# STM32F103C6.net
KiCad netlist of a schematic drawn in Altium Designer
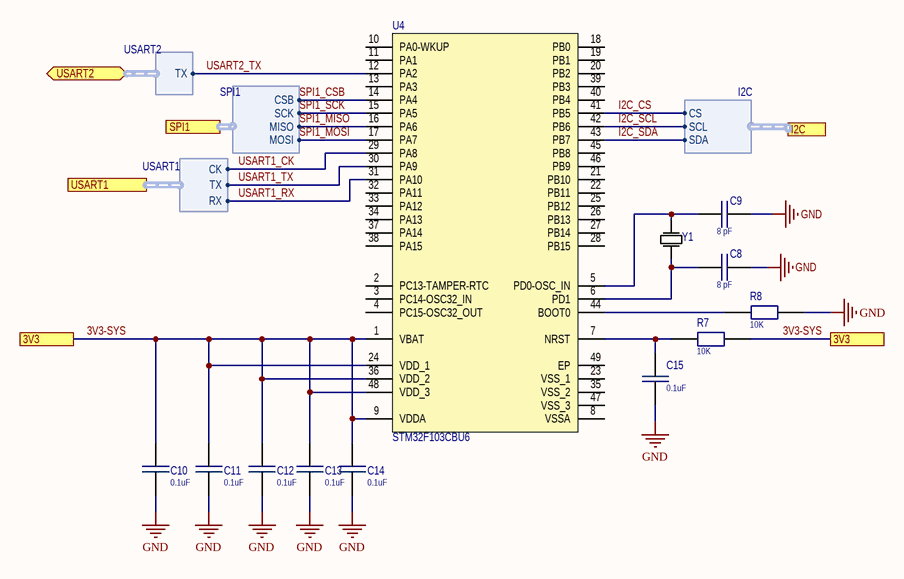
[diagram p0: STM32F103C6.SchDoc]

(export (version "E")
  (design (tool "Eeschema 10.0.6"))
  (components
    (comp (ref "C8")
      (value "8 pF")
      (footprint "C_0805")
      (description "Capacitor")
      (libsource (lib "components") (part "C0805"))
    )
    (comp (ref "C9")
      (value "8 pF")
      (footprint "C_0805")
      (description "Capacitor")
      (libsource (lib "components") (part "C0805"))
    )
    (comp (ref "C10")
      (value "0.1uF")
      (footprint "C_0805")
      (description "Capacitor")
      (libsource (lib "components") (part "C0805"))
    )
    (comp (ref "C11")
      (value "0.1uF")
      (footprint "C_0805")
      (description "Capacitor")
      (libsource (lib "components") (part "C0805"))
    )
    (comp (ref "C12")
      (value "0.1uF")
      (footprint "C_0805")
      (description "Capacitor")
      (libsource (lib "components") (part "C0805"))
    )
    (comp (ref "C13")
      (value "0.1uF")
      (footprint "C_0805")
      (description "Capacitor")
      (libsource (lib "components") (part "C0805"))
    )
    (comp (ref "C14")
      (value "0.1uF")
      (footprint "C_0805")
      (description "Capacitor")
      (libsource (lib "components") (part "C0805"))
    )
    (comp (ref "C15")
      (value "0.1uF")
      (footprint "C_0805")
      (description "Capacitor")
      (libsource (lib "components") (part "C0805"))
    )
    (comp (ref "R7")
      (value "10K")
      (footprint "R_0402")
      (description "Resistor")
      (libsource (lib "components") (part "R0402"))
    )
    (comp (ref "R8")
      (value "10K")
      (footprint "R_0402")
      (description "Resistor")
      (libsource (lib "components") (part "R0402"))
    )
    (comp (ref "U4")
      (value "STM32F103CBU6")
      (footprint "STM-UFQFPN48_M")
      (libsource (lib "modules") (part "STM32F103CBU6"))
    )
    (comp (ref "Y1")
      (value "~")
      (footprint "NX3225GD")
      (description "Crystal Oscillator")
      (libsource (lib "components") (part "NX3225GD"))
    )
  )
  (nets
    (net (code "5") (name "/3V3-SYS") (class "Default")
      (node (ref "C10") (pin "1") (pinfunction "1_1") (pintype "passive"))
      (node (ref "C11") (pin "1") (pinfunction "1_1") (pintype "passive"))
      (node (ref "C12") (pin "1") (pinfunction "1_1") (pintype "passive"))
      (node (ref "C13") (pin "1") (pinfunction "1_1") (pintype "passive"))
      (node (ref "C14") (pin "1") (pinfunction "1_1") (pintype "passive"))
      (node (ref "R7") (pin "2") (pinfunction "2_2") (pintype "passive"))
      (node (ref "U4") (pin "1") (pinfunction "VBAT_1") (pintype "passive"))
      (node (ref "U4") (pin "24") (pinfunction "VDD_1_24") (pintype "passive"))
      (node (ref "U4") (pin "36") (pinfunction "VDD_2_36") (pintype "passive"))
      (node (ref "U4") (pin "48") (pinfunction "VDD_3_48") (pintype "passive"))
      (node (ref "U4") (pin "9") (pinfunction "VDDA_9") (pintype "passive"))
    )
    (net (code "6") (name "/I2C_CS") (class "Default")
      (node (ref "U4") (pin "41") (pinfunction "PB5_41") (pintype "passive"))
    )
    (net (code "7") (name "/I2C_SCL") (class "Default")
      (node (ref "U4") (pin "42") (pinfunction "PB6_42") (pintype "passive"))
    )
    (net (code "8") (name "/I2C_SDA") (class "Default")
      (node (ref "U4") (pin "43") (pinfunction "PB7_43") (pintype "passive"))
    )
    (net (code "9") (name "/SPI1_CSB") (class "Default")
      (node (ref "U4") (pin "14") (pinfunction "PA4_14") (pintype "passive"))
    )
    (net (code "10") (name "/SPI1_MISO") (class "Default")
      (node (ref "U4") (pin "16") (pinfunction "PA6_16") (pintype "passive"))
    )
    (net (code "11") (name "/SPI1_MOSI") (class "Default")
      (node (ref "U4") (pin "17") (pinfunction "PA7_17") (pintype "passive"))
    )
    (net (code "12") (name "/SPI1_SCK") (class "Default")
      (node (ref "U4") (pin "15") (pinfunction "PA5_15") (pintype "passive"))
    )
    (net (code "13") (name "/USART1_CK") (class "Default")
      (node (ref "U4") (pin "29") (pinfunction "PA8_29") (pintype "passive"))
    )
    (net (code "14") (name "/USART1_RX") (class "Default")
      (node (ref "U4") (pin "31") (pinfunction "PA10_31") (pintype "passive"))
    )
    (net (code "15") (name "/USART1_TX") (class "Default")
      (node (ref "U4") (pin "30") (pinfunction "PA9_30") (pintype "passive"))
    )
    (net (code "16") (name "/USART2_TX") (class "Default")
      (node (ref "U4") (pin "12") (pinfunction "PA2_12") (pintype "passive"))
    )
    (net (code "21") (name "GND") (class "Default")
      (node (ref "C10") (pin "2") (pinfunction "2_2") (pintype "passive"))
      (node (ref "C11") (pin "2") (pinfunction "2_2") (pintype "passive"))
      (node (ref "C12") (pin "2") (pinfunction "2_2") (pintype "passive"))
      (node (ref "C13") (pin "2") (pinfunction "2_2") (pintype "passive"))
      (node (ref "C14") (pin "2") (pinfunction "2_2") (pintype "passive"))
      (node (ref "C15") (pin "1") (pinfunction "1_1") (pintype "passive"))
      (node (ref "C8") (pin "2") (pinfunction "2_2") (pintype "passive"))
      (node (ref "C9") (pin "1") (pinfunction "1_1") (pintype "passive"))
      (node (ref "R8") (pin "2") (pinfunction "2_2") (pintype "passive"))
    )
    (net (code "22") (name "Net-(U4-BOOT0)") (class "Default")
      (node (ref "R8") (pin "1") (pinfunction "1_1") (pintype "passive"))
      (node (ref "U4") (pin "44") (pinfunction "BOOT0_44") (pintype "passive"))
    )
    (net (code "23") (name "Net-(U4-NRST)") (class "Default")
      (node (ref "C15") (pin "2") (pinfunction "2_2") (pintype "passive"))
      (node (ref "R7") (pin "1") (pinfunction "1_1") (pintype "passive"))
      (node (ref "U4") (pin "7") (pinfunction "NRST_7") (pintype "passive"))
    )
    (net (code "24") (name "Net-(U4-PD0-OSC_IN)") (class "Default")
      (node (ref "C9") (pin "2") (pinfunction "2_2") (pintype "passive"))
      (node (ref "U4") (pin "5") (pinfunction "PD0-OSC_IN_5") (pintype "passive"))
      (node (ref "Y1") (pin "2") (pinfunction "OSC2_2") (pintype "passive"))
    )
    (net (code "25") (name "Net-(U4-PD1)") (class "Default")
      (node (ref "C8") (pin "1") (pinfunction "1_1") (pintype "passive"))
      (node (ref "U4") (pin "6") (pinfunction "PD1_6") (pintype "passive"))
      (node (ref "Y1") (pin "1") (pinfunction "OSC1_1") (pintype "passive"))
    )
    (net (code "26") (name "unconnected-(U4-EP-Pad49)") (class "Default")
      (node (ref "U4") (pin "49") (pinfunction "EP_49") (pintype "passive"))
    )
    (net (code "27") (name "unconnected-(U4-PA0-WKUP-Pad10)") (class "Default")
      (node (ref "U4") (pin "10") (pinfunction "PA0-WKUP_10") (pintype "passive"))
    )
    (net (code "28") (name "unconnected-(U4-PA1-Pad11)") (class "Default")
      (node (ref "U4") (pin "11") (pinfunction "PA1_11") (pintype "passive"))
    )
    (net (code "29") (name "unconnected-(U4-PA3-Pad13)") (class "Default")
      (node (ref "U4") (pin "13") (pinfunction "PA3_13") (pintype "passive"))
    )
    (net (code "30") (name "unconnected-(U4-PA11-Pad32)") (class "Default")
      (node (ref "U4") (pin "32") (pinfunction "PA11_32") (pintype "passive"))
    )
    (net (code "31") (name "unconnected-(U4-PA12-Pad33)") (class "Default")
      (node (ref "U4") (pin "33") (pinfunction "PA12_33") (pintype "passive"))
    )
    (net (code "32") (name "unconnected-(U4-PA13-Pad34)") (class "Default")
      (node (ref "U4") (pin "34") (pinfunction "PA13_34") (pintype "passive"))
    )
    (net (code "33") (name "unconnected-(U4-PA14-Pad37)") (class "Default")
      (node (ref "U4") (pin "37") (pinfunction "PA14_37") (pintype "passive"))
    )
    (net (code "34") (name "unconnected-(U4-PA15-Pad38)") (class "Default")
      (node (ref "U4") (pin "38") (pinfunction "PA15_38") (pintype "passive"))
    )
    (net (code "35") (name "unconnected-(U4-PB0-Pad18)") (class "Default")
      (node (ref "U4") (pin "18") (pinfunction "PB0_18") (pintype "passive"))
    )
    (net (code "36") (name "unconnected-(U4-PB1-Pad19)") (class "Default")
      (node (ref "U4") (pin "19") (pinfunction "PB1_19") (pintype "passive"))
    )
    (net (code "37") (name "unconnected-(U4-PB2-Pad20)") (class "Default")
      (node (ref "U4") (pin "20") (pinfunction "PB2_20") (pintype "passive"))
    )
    (net (code "38") (name "unconnected-(U4-PB3-Pad39)") (class "Default")
      (node (ref "U4") (pin "39") (pinfunction "PB3_39") (pintype "passive"))
    )
    (net (code "39") (name "unconnected-(U4-PB4-Pad40)") (class "Default")
      (node (ref "U4") (pin "40") (pinfunction "PB4_40") (pintype "passive"))
    )
    (net (code "40") (name "unconnected-(U4-PB8-Pad45)") (class "Default")
      (node (ref "U4") (pin "45") (pinfunction "PB8_45") (pintype "passive"))
    )
    (net (code "41") (name "unconnected-(U4-PB9-Pad46)") (class "Default")
      (node (ref "U4") (pin "46") (pinfunction "PB9_46") (pintype "passive"))
    )
    (net (code "42") (name "unconnected-(U4-PB10-Pad21)") (class "Default")
      (node (ref "U4") (pin "21") (pinfunction "PB10_21") (pintype "passive"))
    )
    (net (code "43") (name "unconnected-(U4-PB11-Pad22)") (class "Default")
      (node (ref "U4") (pin "22") (pinfunction "PB11_22") (pintype "passive"))
    )
    (net (code "44") (name "unconnected-(U4-PB12-Pad25)") (class "Default")
      (node (ref "U4") (pin "25") (pinfunction "PB12_25") (pintype "passive"))
    )
    (net (code "45") (name "unconnected-(U4-PB13-Pad26)") (class "Default")
      (node (ref "U4") (pin "26") (pinfunction "PB13_26") (pintype "passive"))
    )
    (net (code "46") (name "unconnected-(U4-PB14-Pad27)") (class "Default")
      (node (ref "U4") (pin "27") (pinfunction "PB14_27") (pintype "passive"))
    )
    (net (code "47") (name "unconnected-(U4-PB15-Pad28)") (class "Default")
      (node (ref "U4") (pin "28") (pinfunction "PB15_28") (pintype "passive"))
    )
    (net (code "48") (name "unconnected-(U4-PC13-TAMPER-RTC-Pad2)") (class "Default")
      (node (ref "U4") (pin "2") (pinfunction "PC13-TAMPER-RTC_2") (pintype "passive"))
    )
    (net (code "49") (name "unconnected-(U4-PC14-OSC32_IN-Pad3)") (class "Default")
      (node (ref "U4") (pin "3") (pinfunction "PC14-OSC32_IN_3") (pintype "passive"))
    )
    (net (code "50") (name "unconnected-(U4-PC15-OSC32_OUT-Pad4)") (class "Default")
      (node (ref "U4") (pin "4") (pinfunction "PC15-OSC32_OUT_4") (pintype "passive"))
    )
    (net (code "51") (name "unconnected-(U4-VSSA-Pad8)") (class "Default")
      (node (ref "U4") (pin "8") (pinfunction "VSSA_8") (pintype "passive"))
    )
    (net (code "52") (name "unconnected-(U4-VSS_1-Pad23)") (class "Default")
      (node (ref "U4") (pin "23") (pinfunction "VSS_1_23") (pintype "passive"))
    )
    (net (code "53") (name "unconnected-(U4-VSS_2-Pad35)") (class "Default")
      (node (ref "U4") (pin "35") (pinfunction "VSS_2_35") (pintype "passive"))
    )
    (net (code "54") (name "unconnected-(U4-VSS_3-Pad47)") (class "Default")
      (node (ref "U4") (pin "47") (pinfunction "VSS_3_47") (pintype "passive"))
    )
  )
)
